# Switches_Blocks.net
KiCad netlist of a schematic drawn in Altium Designer
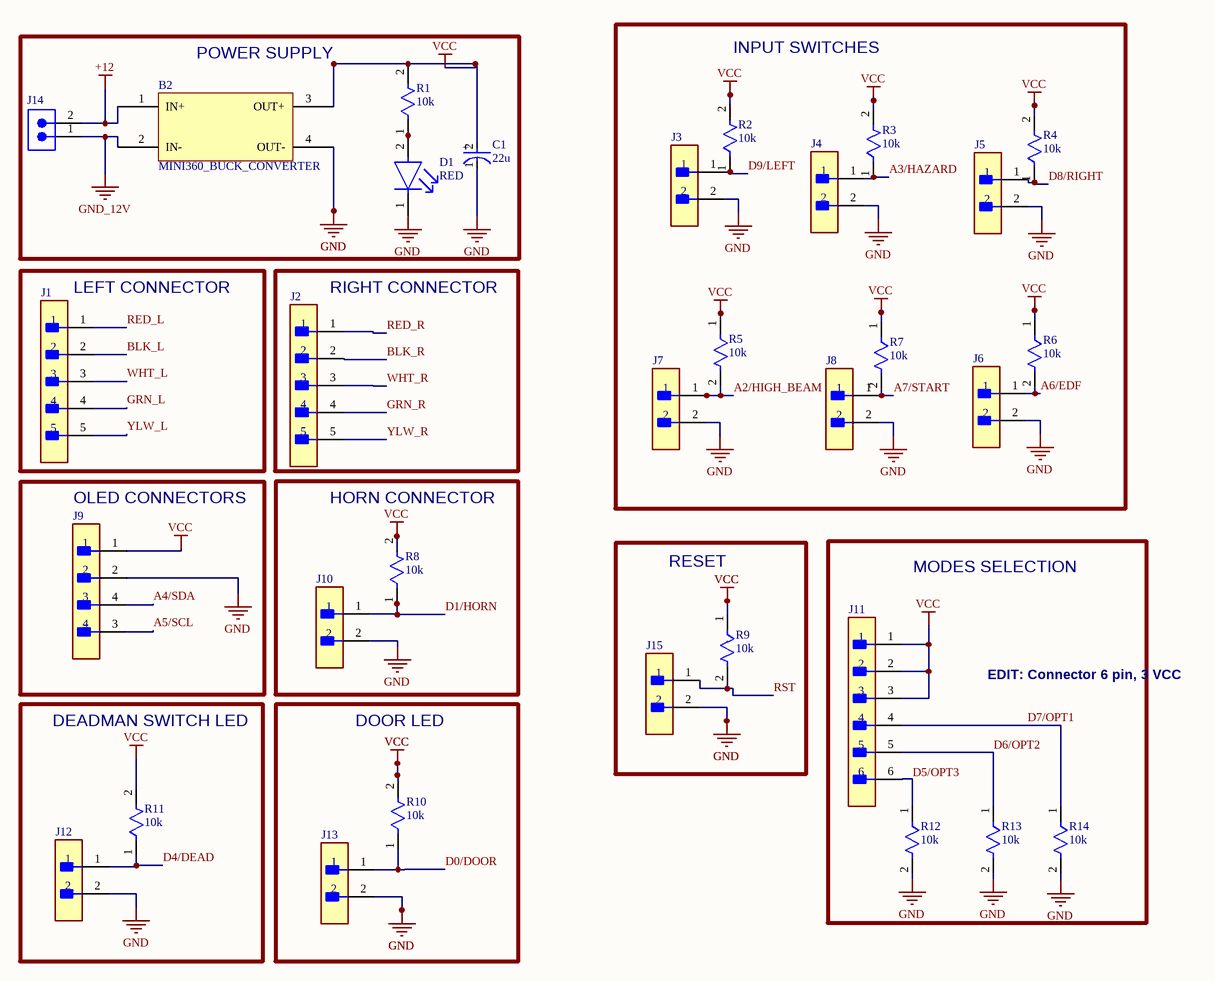
[diagram p0: Switches + Blocks.SchDoc]

(export (version "E")
  (design (tool "Eeschema 10.0.6"))
  (components
    (comp (ref "B2")
      (value "MINI360_BUCK_CONVERTER")
      (footprint "MINI360_BUCK_CONVERTER")
      (libsource (lib "Buck_Converter") (part "MINI360_BUCK_CONVERTER"))
    )
    (comp (ref "C1")
      (value "22u")
      (footprint "FP-RAD-TH-D_5_0_5-L_11_1-MFG")
      (description "Aluminum Electrolytic Capacitors (Radial Lead Type) AEC-Q200 Qualified 22uF ±20% 50V")
      (fields (field (name "TOLERANCE") "20%"))
      (libsource (lib "Altium Content Vault") (part "a00bbbee19879c290e62620ae7e47b1"))
    )
    (comp (ref "D1")
      (value "RED")
      (footprint "FP-6_544-5255_01-4-MFG")
      (description "TLLG4400 Led, Pcb, Green, 0.63MCD, 3MM, T-1, 7MA, 1.9V, 565NM, 25DEG, 20V, 20MW, -40")
      (libsource (lib "Altium Content Vault") (part "8706943c75ba83719d021d2fdc84c58"))
    )
    (comp (ref "J1")
      (value "B5B-XH-AM(LF)(SN)")
      (footprint "FP-B5B-XH-AM_LF_SN-MFG")
      (description "CONN HEADER VERT 5POS 2.5MM")
      (libsource (lib "Altium Content Vault") (part "bf93c07fd2649a848d0ec8585582aab"))
    )
    (comp (ref "J2")
      (value "B5B-XH-AM(LF)(SN)")
      (footprint "FP-B5B-XH-AM_LF_SN-MFG")
      (description "CONN HEADER VERT 5POS 2.5MM")
      (libsource (lib "Altium Content Vault") (part "bf93c07fd2649a848d0ec8585582aab"))
    )
    (comp (ref "J3")
      (value "B2B-XH-A(LF)(SN)")
      (footprint "FP-B2B-XH-A_LF_SN-MFG")
      (description "CONN HEADER VERT 2POS 2.5MM")
      (libsource (lib "Altium Content Vault") (part "3bc925449376181038e59eaffc5286c"))
    )
    (comp (ref "J4")
      (value "B2B-XH-A(LF)(SN)")
      (footprint "FP-B2B-XH-A_LF_SN-MFG")
      (description "CONN HEADER VERT 2POS 2.5MM")
      (libsource (lib "Altium Content Vault") (part "3bc925449376181038e59eaffc5286c"))
    )
    (comp (ref "J5")
      (value "B2B-XH-A(LF)(SN)")
      (footprint "FP-B2B-XH-A_LF_SN-MFG")
      (description "CONN HEADER VERT 2POS 2.5MM")
      (libsource (lib "Altium Content Vault") (part "3bc925449376181038e59eaffc5286c"))
    )
    (comp (ref "J6")
      (value "B2B-XH-A(LF)(SN)")
      (footprint "FP-B2B-XH-A_LF_SN-MFG")
      (description "CONN HEADER VERT 2POS 2.5MM")
      (libsource (lib "Altium Content Vault") (part "3bc925449376181038e59eaffc5286c"))
    )
    (comp (ref "J7")
      (value "B2B-XH-A(LF)(SN)")
      (footprint "FP-B2B-XH-A_LF_SN-MFG")
      (description "CONN HEADER VERT 2POS 2.5MM")
      (libsource (lib "Altium Content Vault") (part "3bc925449376181038e59eaffc5286c"))
    )
    (comp (ref "J8")
      (value "B2B-XH-A(LF)(SN)")
      (footprint "FP-B2B-XH-A_LF_SN-MFG")
      (description "CONN HEADER VERT 2POS 2.5MM")
      (libsource (lib "Altium Content Vault") (part "3bc925449376181038e59eaffc5286c"))
    )
    (comp (ref "J9")
      (value "B4B-XH-A(LF)(SN)")
      (footprint "FP-B4B-XH-A_LF_SN-MFG")
      (description "CONN HEADER VERT 4POS 2.5MM")
      (libsource (lib "Altium Content Vault") (part "299a8cea1bdcbc3624fe62c390fa72c"))
    )
    (comp (ref "J10")
      (value "B2B-XH-A(LF)(SN)")
      (footprint "FP-B2B-XH-A_LF_SN-MFG")
      (description "CONN HEADER VERT 2POS 2.5MM")
      (libsource (lib "Altium Content Vault") (part "3bc925449376181038e59eaffc5286c"))
    )
    (comp (ref "J11")
      (value "B6B-XH-AM(LF)(SN)")
      (footprint "FP-B6B-XH-AM_LF_SN-MFG")
      (description "CONN HEADER VERT 6POS 2.5MM")
      (libsource (lib "Altium Content Vault") (part "f2cb566baf1c37ab5a3b8e90bbeafd6"))
    )
    (comp (ref "J12")
      (value "B2B-XH-A(LF)(SN)")
      (footprint "FP-B2B-XH-A_LF_SN-MFG")
      (description "CONN HEADER VERT 2POS 2.5MM")
      (libsource (lib "Altium Content Vault") (part "3bc925449376181038e59eaffc5286c"))
    )
    (comp (ref "J13")
      (value "B2B-XH-A(LF)(SN)")
      (footprint "FP-B2B-XH-A_LF_SN-MFG")
      (description "CONN HEADER VERT 2POS 2.5MM")
      (libsource (lib "Altium Content Vault") (part "3bc925449376181038e59eaffc5286c"))
    )
    (comp (ref "J14")
      (value "691312510002")
      (footprint "691312510002")
      (fields (field (name "VOLTAGE") "300V"))
      (libsource (lib "Altium Content Vault") (part "TBL - 1R - 02P - Male"))
    )
    (comp (ref "J15")
      (value "B2B-XH-A(LF)(SN)")
      (footprint "FP-B2B-XH-A_LF_SN-MFG")
      (description "CONN HEADER VERT 2POS 2.5MM")
      (libsource (lib "Altium Content Vault") (part "3bc925449376181038e59eaffc5286c"))
    )
    (comp (ref "R1")
      (value "10k")
      (footprint "PCBComponent_1")
      (libsource (lib "RES_0.125W_AXIAL") (part "RES"))
    )
    (comp (ref "R2")
      (value "10k")
      (footprint "PCBComponent_1")
      (libsource (lib "RES_0.125W_AXIAL") (part "RES"))
    )
    (comp (ref "R3")
      (value "10k")
      (footprint "PCBComponent_1")
      (libsource (lib "RES_0.125W_AXIAL") (part "RES"))
    )
    (comp (ref "R4")
      (value "10k")
      (footprint "PCBComponent_1")
      (libsource (lib "RES_0.125W_AXIAL") (part "RES"))
    )
    (comp (ref "R5")
      (value "10k")
      (footprint "PCBComponent_1")
      (libsource (lib "RES_0.125W_AXIAL") (part "RES"))
    )
    (comp (ref "R6")
      (value "10k")
      (footprint "PCBComponent_1")
      (libsource (lib "RES_0.125W_AXIAL") (part "RES"))
    )
    (comp (ref "R7")
      (value "10k")
      (footprint "PCBComponent_1")
      (libsource (lib "RES_0.125W_AXIAL") (part "RES"))
    )
    (comp (ref "R8")
      (value "10k")
      (footprint "PCBComponent_1")
      (libsource (lib "RES_0.125W_AXIAL") (part "RES"))
    )
    (comp (ref "R9")
      (value "10k")
      (footprint "PCBComponent_1")
      (libsource (lib "RES_0.125W_AXIAL") (part "RES"))
    )
    (comp (ref "R10")
      (value "10k")
      (footprint "PCBComponent_1")
      (libsource (lib "RES_0.125W_AXIAL") (part "RES"))
    )
    (comp (ref "R11")
      (value "10k")
      (footprint "PCBComponent_1")
      (libsource (lib "RES_0.125W_AXIAL") (part "RES"))
    )
    (comp (ref "R12")
      (value "10k")
      (footprint "PCBComponent_1")
      (libsource (lib "RES_0.125W_AXIAL") (part "RES"))
    )
    (comp (ref "R13")
      (value "10k")
      (footprint "PCBComponent_1")
      (libsource (lib "RES_0.125W_AXIAL") (part "RES"))
    )
    (comp (ref "R14")
      (value "10k")
      (footprint "PCBComponent_1")
      (libsource (lib "RES_0.125W_AXIAL") (part "RES"))
    )
  )
  (nets
    (net (code "1") (name "+12") (class "Default")
      (node (ref "B2") (pin "1") (pinfunction "IN+_1") (pintype "passive"))
      (node (ref "J14") (pin "2") (pinfunction "2_2") (pintype "passive"))
    )
    (net (code "2") (name "/A2{slash}HIGH_BEAM") (class "Default")
      (node (ref "J7") (pin "1") (pinfunction "1_1") (pintype "passive"))
      (node (ref "R5") (pin "2") (pinfunction "2_2") (pintype "passive"))
    )
    (net (code "3") (name "/A3{slash}HAZARD") (class "Default")
      (node (ref "J4") (pin "1") (pinfunction "1_1") (pintype "passive"))
      (node (ref "R3") (pin "1") (pinfunction "1_1") (pintype "passive"))
    )
    (net (code "4") (name "/A4{slash}SDA") (class "Default")
      (node (ref "J9") (pin "4") (pinfunction "4_4") (pintype "passive"))
    )
    (net (code "5") (name "/A5{slash}SCL") (class "Default")
      (node (ref "J9") (pin "3") (pinfunction "3_3") (pintype "passive"))
    )
    (net (code "6") (name "/A6{slash}EDF") (class "Default")
      (node (ref "J6") (pin "1") (pinfunction "1_1") (pintype "passive"))
      (node (ref "R6") (pin "2") (pinfunction "2_2") (pintype "passive"))
    )
    (net (code "7") (name "/A7{slash}START") (class "Default")
      (node (ref "J8") (pin "1") (pinfunction "1_1") (pintype "passive"))
      (node (ref "R7") (pin "2") (pinfunction "2_2") (pintype "passive"))
    )
    (net (code "8") (name "/BLK_L") (class "Default")
      (node (ref "J1") (pin "2") (pinfunction "2_2") (pintype "passive"))
    )
    (net (code "9") (name "/BLK_R") (class "Default")
      (node (ref "J2") (pin "2") (pinfunction "2_2") (pintype "passive"))
    )
    (net (code "10") (name "/D0{slash}DOOR") (class "Default")
      (node (ref "J13") (pin "1") (pinfunction "1_1") (pintype "passive"))
      (node (ref "R10") (pin "1") (pinfunction "1_1") (pintype "passive"))
    )
    (net (code "11") (name "/D1{slash}HORN") (class "Default")
      (node (ref "J10") (pin "1") (pinfunction "1_1") (pintype "passive"))
      (node (ref "R8") (pin "1") (pinfunction "1_1") (pintype "passive"))
    )
    (net (code "12") (name "/D4{slash}DEAD") (class "Default")
      (node (ref "J12") (pin "1") (pinfunction "1_1") (pintype "passive"))
      (node (ref "R11") (pin "1") (pinfunction "1_1") (pintype "passive"))
    )
    (net (code "13") (name "/D5{slash}OPT3") (class "Default")
      (node (ref "J11") (pin "6") (pinfunction "6_6") (pintype "passive"))
      (node (ref "R12") (pin "1") (pinfunction "1_1") (pintype "passive"))
    )
    (net (code "14") (name "/D6{slash}OPT2") (class "Default")
      (node (ref "J11") (pin "5") (pinfunction "5_5") (pintype "passive"))
      (node (ref "R13") (pin "1") (pinfunction "1_1") (pintype "passive"))
    )
    (net (code "15") (name "/D7{slash}OPT1") (class "Default")
      (node (ref "J11") (pin "4") (pinfunction "4_4") (pintype "passive"))
      (node (ref "R14") (pin "1") (pinfunction "1_1") (pintype "passive"))
    )
    (net (code "16") (name "/D8{slash}RIGHT") (class "Default")
      (node (ref "J5") (pin "1") (pinfunction "1_1") (pintype "passive"))
      (node (ref "R4") (pin "1") (pinfunction "1_1") (pintype "passive"))
    )
    (net (code "17") (name "/D9{slash}LEFT") (class "Default")
      (node (ref "J3") (pin "1") (pinfunction "1_1") (pintype "passive"))
      (node (ref "R2") (pin "1") (pinfunction "1_1") (pintype "passive"))
    )
    (net (code "18") (name "/GRN_L") (class "Default")
      (node (ref "J1") (pin "4") (pinfunction "4_4") (pintype "passive"))
    )
    (net (code "19") (name "/GRN_R") (class "Default")
      (node (ref "J2") (pin "4") (pinfunction "4_4") (pintype "passive"))
    )
    (net (code "20") (name "/RED_L") (class "Default")
      (node (ref "J1") (pin "1") (pinfunction "1_1") (pintype "passive"))
    )
    (net (code "21") (name "/RED_R") (class "Default")
      (node (ref "J2") (pin "1") (pinfunction "1_1") (pintype "passive"))
    )
    (net (code "22") (name "/RST") (class "Default")
      (node (ref "J15") (pin "1") (pinfunction "1_1") (pintype "passive"))
      (node (ref "R9") (pin "2") (pinfunction "2_2") (pintype "passive"))
    )
    (net (code "23") (name "/WHT_L") (class "Default")
      (node (ref "J1") (pin "3") (pinfunction "3_3") (pintype "passive"))
    )
    (net (code "24") (name "/WHT_R") (class "Default")
      (node (ref "J2") (pin "3") (pinfunction "3_3") (pintype "passive"))
    )
    (net (code "25") (name "/YLW_L") (class "Default")
      (node (ref "J1") (pin "5") (pinfunction "5_5") (pintype "passive"))
    )
    (net (code "26") (name "/YLW_R") (class "Default")
      (node (ref "J2") (pin "5") (pinfunction "5_5") (pintype "passive"))
    )
    (net (code "27") (name "GND") (class "Default")
      (node (ref "B2") (pin "4") (pinfunction "OUT-_4") (pintype "passive"))
      (node (ref "C1") (pin "1") (pinfunction "C_1") (pintype "passive"))
      (node (ref "D1") (pin "1") (pinfunction "C_1") (pintype "passive"))
      (node (ref "J10") (pin "2") (pinfunction "2_2") (pintype "passive"))
      (node (ref "J12") (pin "2") (pinfunction "2_2") (pintype "passive"))
      (node (ref "J13") (pin "2") (pinfunction "2_2") (pintype "passive"))
      (node (ref "J15") (pin "2") (pinfunction "2_2") (pintype "passive"))
      (node (ref "J3") (pin "2") (pinfunction "2_2") (pintype "passive"))
      (node (ref "J4") (pin "2") (pinfunction "2_2") (pintype "passive"))
      (node (ref "J5") (pin "2") (pinfunction "2_2") (pintype "passive"))
      (node (ref "J6") (pin "2") (pinfunction "2_2") (pintype "passive"))
      (node (ref "J7") (pin "2") (pinfunction "2_2") (pintype "passive"))
      (node (ref "J8") (pin "2") (pinfunction "2_2") (pintype "passive"))
      (node (ref "J9") (pin "2") (pinfunction "2_2") (pintype "passive"))
      (node (ref "R12") (pin "2") (pinfunction "2_2") (pintype "passive"))
      (node (ref "R13") (pin "2") (pinfunction "2_2") (pintype "passive"))
      (node (ref "R14") (pin "2") (pinfunction "2_2") (pintype "passive"))
    )
    (net (code "28") (name "GND_12V") (class "Default")
      (node (ref "B2") (pin "2") (pinfunction "IN-_2") (pintype "passive"))
      (node (ref "J14") (pin "1") (pinfunction "1_1") (pintype "passive"))
    )
    (net (code "29") (name "Net-(D1-A)") (class "Default")
      (node (ref "D1") (pin "2") (pinfunction "A_2") (pintype "passive"))
      (node (ref "R1") (pin "1") (pinfunction "1_1") (pintype "passive"))
    )
    (net (code "30") (name "VCC") (class "Default")
      (node (ref "B2") (pin "3") (pinfunction "OUT+_3") (pintype "passive"))
      (node (ref "C1") (pin "2") (pinfunction "A_2") (pintype "passive"))
      (node (ref "J11") (pin "1") (pinfunction "1_1") (pintype "passive"))
      (node (ref "J11") (pin "2") (pinfunction "2_2") (pintype "passive"))
      (node (ref "J11") (pin "3") (pinfunction "3_3") (pintype "passive"))
      (node (ref "J9") (pin "1") (pinfunction "1_1") (pintype "passive"))
      (node (ref "R1") (pin "2") (pinfunction "2_2") (pintype "passive"))
      (node (ref "R10") (pin "2") (pinfunction "2_2") (pintype "passive"))
      (node (ref "R11") (pin "2") (pinfunction "2_2") (pintype "passive"))
      (node (ref "R2") (pin "2") (pinfunction "2_2") (pintype "passive"))
      (node (ref "R3") (pin "2") (pinfunction "2_2") (pintype "passive"))
      (node (ref "R4") (pin "2") (pinfunction "2_2") (pintype "passive"))
      (node (ref "R5") (pin "1") (pinfunction "1_1") (pintype "passive"))
      (node (ref "R6") (pin "1") (pinfunction "1_1") (pintype "passive"))
      (node (ref "R7") (pin "1") (pinfunction "1_1") (pintype "passive"))
      (node (ref "R8") (pin "2") (pinfunction "2_2") (pintype "passive"))
      (node (ref "R9") (pin "1") (pinfunction "1_1") (pintype "passive"))
    )
  )
)
